# Microcontroller_IO.net
KiCad netlist of a schematic drawn in Altium Designer
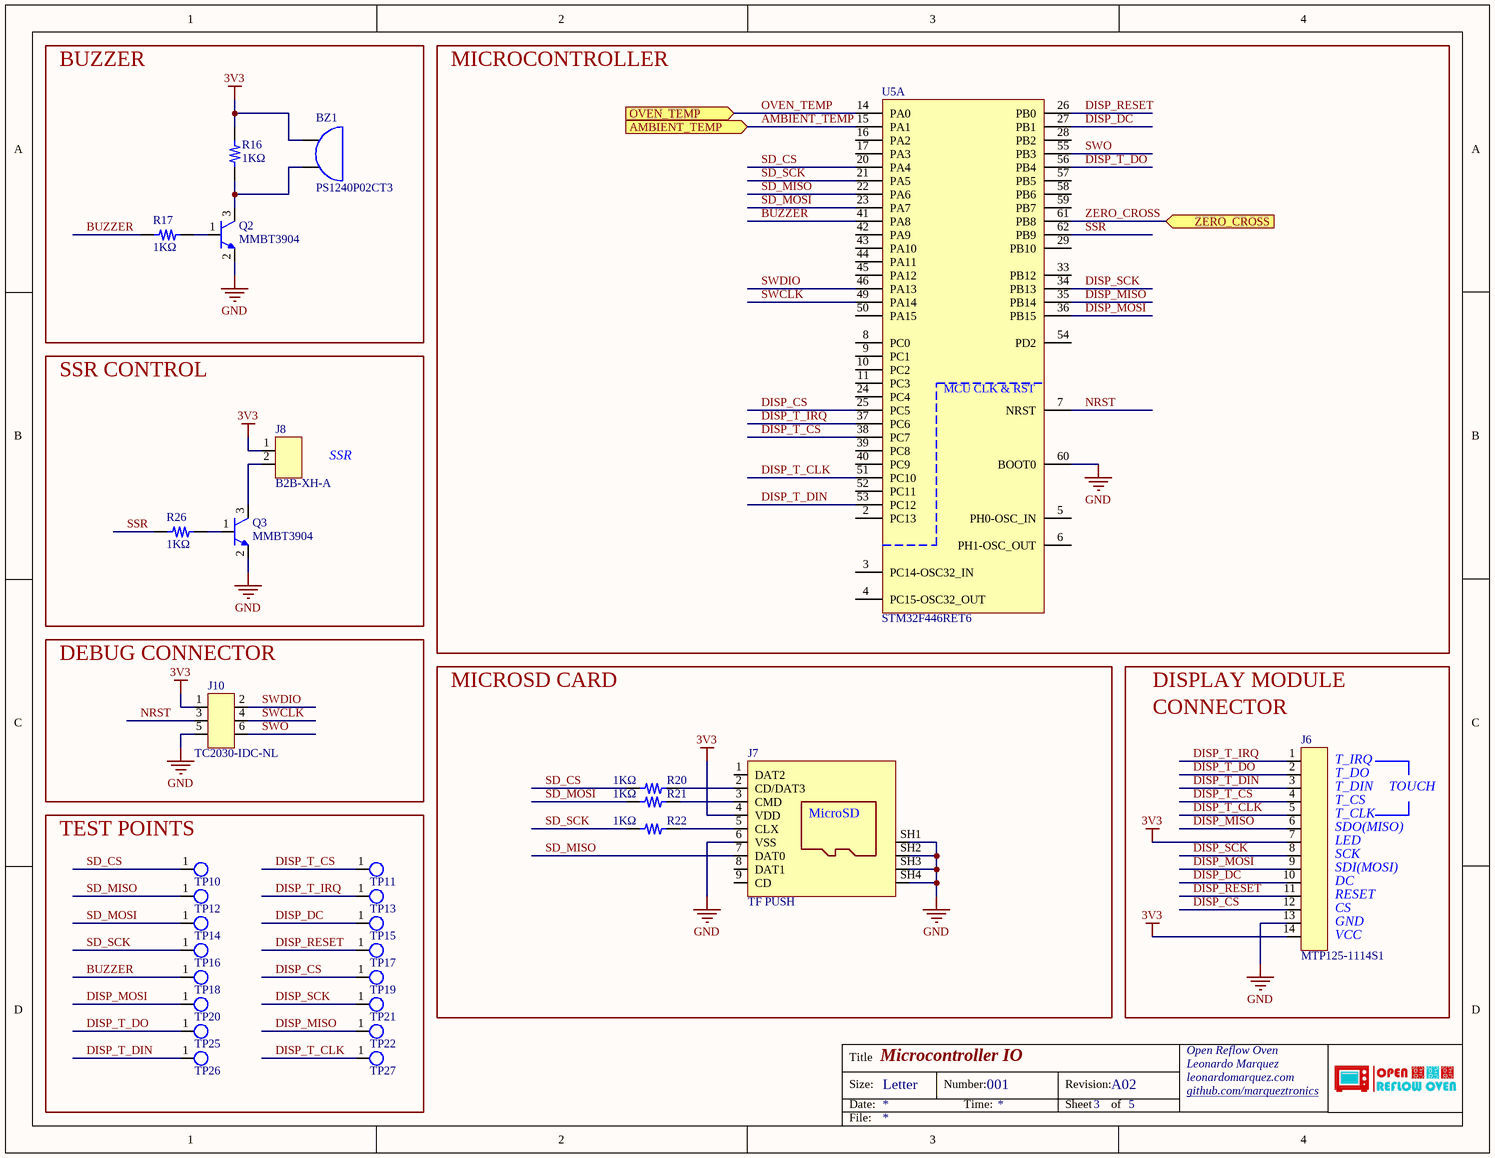
[diagram p0: Microcontroller IO.SchDoc]

(export (version "E")
  (design (tool "Eeschema 10.0.6"))
  (components
    (comp (ref "BZ1")
      (value "PS1240P02CT3")
      (footprint "PS1240P02CT3")
      (description "60dB Externally Driven Externally Driven 4kHz Plugin,D=12.2mm Buzzers ROHS")
      (fields (field (name "MANUFACTURER") "TDK"))
      (libsource (lib "REFLOW_CONTROLLER") (part "BZ-4KHZ-30V-PS1240P02CT3"))
    )
    (comp (ref "J6")
      (value "MTP125-1114S1")
      (footprint "MTP125-1114S1")
      (description "14P 2.54mm Single Row 1x14P Plugin,P=2.54mm Pin Headers ROHS")
      (fields (field (name "MANUFACTURER") "MINTRON"))
      (libsource (lib "REFLOW_CONTROLLER") (part "J-14P-HDR-MALE-2.54MM-MTP125-1114S1"))
    )
    (comp (ref "J7")
      (value "TF PUSH")
      (footprint "TF_PUSH")
      (fields (field (name "MANUFACTURER") "SHOU HAN"))
      (libsource (lib "REFLOW_CONTROLLER") (part "J-MICROSD-TF_PUSH"))
    )
    (comp (ref "J8")
      (value "B2B-XH-A")
      (footprint "B2B-XH-A")
      (description "1x2P 2P XH 1 2.5mm 2 Brass Plugin,P=2.5mm Wire To Board Connector ROHS")
      (fields
        (field (name "MANUFACTURER") "JST")
        (field (name "MANUFACTURER PART NUMBER") "B2B-XH-A(LF)(SN)")
      )
      (libsource (lib "REFLOW_CONTROLLER") (part "J-2P-2.5MM-B2B-XH-A"))
    )
    (comp (ref "J10")
      (value "TC2030-IDC-NL")
      (footprint "TC2030-IDC-NL-FP")
      (description "“No Legs” 6-pin Plug-of-Nails™ Cable fitted with a 6-pin 0.1″ pitch ribbon connector")
      (fields (field (name "MANUFACTURER") "Tag-Connect"))
      (libsource (lib "REFLOW_CONTROLLER") (part "J-6P-TAG-CONNECT-TC2030-IDC-NL-FP"))
    )
    (comp (ref "Q2")
      (value "MMBT3904")
      (footprint "SOT-23")
      (description "40V 250mW 200mA NPN SOT-23 Bipolar Transistors - BJT ROHS")
      (fields (field (name "MANUFACTURER") "Nexperia"))
      (libsource (lib "REFLOW_CONTROLLER") (part "Q-NPN-40V-0.2A-SOT-23"))
    )
    (comp (ref "Q3")
      (value "MMBT3904")
      (footprint "SOT-23")
      (description "40V 250mW 200mA NPN SOT-23 Bipolar Transistors - BJT ROHS")
      (fields (field (name "MANUFACTURER") "Nexperia"))
      (libsource (lib "REFLOW_CONTROLLER") (part "Q-NPN-40V-0.2A-SOT-23"))
    )
    (comp (ref "R16")
      (value "1KΩ")
      (footprint "R0603")
      (description "100mW Thick Film Resistors 75V ±100ppm/℃ ±1% 1kΩ 0603 Chip Resistor - Surface Mount ROHS")
      (fields
        (field (name "MANUFACTURER") "Yageo")
        (field (name "MANUFACTURER PART NUMBER") "RC0603FR-071KL")
      )
      (libsource (lib "REFLOW_CONTROLLER") (part "R-1K-1/10W-R0603"))
    )
    (comp (ref "R17")
      (value "1KΩ")
      (footprint "R0603")
      (description "100mW Thick Film Resistors 75V ±100ppm/℃ ±1% 1kΩ 0603 Chip Resistor - Surface Mount ROHS")
      (fields
        (field (name "MANUFACTURER") "Yageo")
        (field (name "MANUFACTURER PART NUMBER") "RC0603FR-071KL")
      )
      (libsource (lib "REFLOW_CONTROLLER") (part "R-1K-1/10W-R0603"))
    )
    (comp (ref "R20")
      (value "1KΩ")
      (footprint "R0603")
      (description "100mW Thick Film Resistors 75V ±100ppm/℃ ±1% 1kΩ 0603 Chip Resistor - Surface Mount ROHS")
      (fields
        (field (name "MANUFACTURER") "Yageo")
        (field (name "MANUFACTURER PART NUMBER") "RC0603FR-071KL")
      )
      (libsource (lib "REFLOW_CONTROLLER") (part "R-1K-1/10W-R0603"))
    )
    (comp (ref "R21")
      (value "1KΩ")
      (footprint "R0603")
      (description "100mW Thick Film Resistors 75V ±100ppm/℃ ±1% 1kΩ 0603 Chip Resistor - Surface Mount ROHS")
      (fields
        (field (name "MANUFACTURER") "Yageo")
        (field (name "MANUFACTURER PART NUMBER") "RC0603FR-071KL")
      )
      (libsource (lib "REFLOW_CONTROLLER") (part "R-1K-1/10W-R0603"))
    )
    (comp (ref "R22")
      (value "1KΩ")
      (footprint "R0603")
      (description "100mW Thick Film Resistors 75V ±100ppm/℃ ±1% 1kΩ 0603 Chip Resistor - Surface Mount ROHS")
      (fields
        (field (name "MANUFACTURER") "Yageo")
        (field (name "MANUFACTURER PART NUMBER") "RC0603FR-071KL")
      )
      (libsource (lib "REFLOW_CONTROLLER") (part "R-1K-1/10W-R0603"))
    )
    (comp (ref "R26")
      (value "1KΩ")
      (footprint "R0603")
      (description "100mW Thick Film Resistors 75V ±100ppm/℃ ±1% 1kΩ 0603 Chip Resistor - Surface Mount ROHS")
      (fields
        (field (name "MANUFACTURER") "Yageo")
        (field (name "MANUFACTURER PART NUMBER") "RC0603FR-071KL")
      )
      (libsource (lib "REFLOW_CONTROLLER") (part "R-1K-1/10W-R0603"))
    )
    (comp (ref "TP10")
      (value "TP-1MM-ROUND")
      (footprint "TP-1MM-ROUND")
      (description "Round Test Point 1mm Dia")
      (libsource (lib "REFLOW_CONTROLLER") (part "TP-1MM-ROUND"))
    )
    (comp (ref "TP11")
      (value "TP-1MM-ROUND")
      (footprint "TP-1MM-ROUND")
      (description "Round Test Point 1mm Dia")
      (libsource (lib "REFLOW_CONTROLLER") (part "TP-1MM-ROUND"))
    )
    (comp (ref "TP12")
      (value "TP-1MM-ROUND")
      (footprint "TP-1MM-ROUND")
      (description "Round Test Point 1mm Dia")
      (libsource (lib "REFLOW_CONTROLLER") (part "TP-1MM-ROUND"))
    )
    (comp (ref "TP13")
      (value "TP-1MM-ROUND")
      (footprint "TP-1MM-ROUND")
      (description "Round Test Point 1mm Dia")
      (libsource (lib "REFLOW_CONTROLLER") (part "TP-1MM-ROUND"))
    )
    (comp (ref "TP14")
      (value "TP-1MM-ROUND")
      (footprint "TP-1MM-ROUND")
      (description "Round Test Point 1mm Dia")
      (libsource (lib "REFLOW_CONTROLLER") (part "TP-1MM-ROUND"))
    )
    (comp (ref "TP15")
      (value "TP-1MM-ROUND")
      (footprint "TP-1MM-ROUND")
      (description "Round Test Point 1mm Dia")
      (libsource (lib "REFLOW_CONTROLLER") (part "TP-1MM-ROUND"))
    )
    (comp (ref "TP16")
      (value "TP-1MM-ROUND")
      (footprint "TP-1MM-ROUND")
      (description "Round Test Point 1mm Dia")
      (libsource (lib "REFLOW_CONTROLLER") (part "TP-1MM-ROUND"))
    )
    (comp (ref "TP17")
      (value "TP-1MM-ROUND")
      (footprint "TP-1MM-ROUND")
      (description "Round Test Point 1mm Dia")
      (libsource (lib "REFLOW_CONTROLLER") (part "TP-1MM-ROUND"))
    )
    (comp (ref "TP18")
      (value "TP-1MM-ROUND")
      (footprint "TP-1MM-ROUND")
      (description "Round Test Point 1mm Dia")
      (libsource (lib "REFLOW_CONTROLLER") (part "TP-1MM-ROUND"))
    )
    (comp (ref "TP19")
      (value "TP-1MM-ROUND")
      (footprint "TP-1MM-ROUND")
      (description "Round Test Point 1mm Dia")
      (libsource (lib "REFLOW_CONTROLLER") (part "TP-1MM-ROUND"))
    )
    (comp (ref "TP20")
      (value "TP-1MM-ROUND")
      (footprint "TP-1MM-ROUND")
      (description "Round Test Point 1mm Dia")
      (libsource (lib "REFLOW_CONTROLLER") (part "TP-1MM-ROUND"))
    )
    (comp (ref "TP21")
      (value "TP-1MM-ROUND")
      (footprint "TP-1MM-ROUND")
      (description "Round Test Point 1mm Dia")
      (libsource (lib "REFLOW_CONTROLLER") (part "TP-1MM-ROUND"))
    )
    (comp (ref "TP22")
      (value "TP-1MM-ROUND")
      (footprint "TP-1MM-ROUND")
      (description "Round Test Point 1mm Dia")
      (libsource (lib "REFLOW_CONTROLLER") (part "TP-1MM-ROUND"))
    )
    (comp (ref "TP25")
      (value "TP-1MM-ROUND")
      (footprint "TP-1MM-ROUND")
      (description "Round Test Point 1mm Dia")
      (libsource (lib "REFLOW_CONTROLLER") (part "TP-1MM-ROUND"))
    )
    (comp (ref "TP26")
      (value "TP-1MM-ROUND")
      (footprint "TP-1MM-ROUND")
      (description "Round Test Point 1mm Dia")
      (libsource (lib "REFLOW_CONTROLLER") (part "TP-1MM-ROUND"))
    )
    (comp (ref "TP27")
      (value "TP-1MM-ROUND")
      (footprint "TP-1MM-ROUND")
      (description "Round Test Point 1mm Dia")
      (libsource (lib "REFLOW_CONTROLLER") (part "TP-1MM-ROUND"))
    )
    (comp (ref "U5")
      (value "STM32F446RET6")
      (footprint "LQFP-64_10X10")
      (description "512KB 1.7V~3.6V ARM-M4 128KB 180MHz FLASH 50 LQFP-64(10x10) Microcontrollers (MCU/MPU/SOC) ROHS")
      (fields (field (name "MANUFACTURER") "STMicroelectronics"))
      (libsource (lib "REFLOW_CONTROLLER") (part "U-STM32F446RET6-LQFP-64_10X10"))
    )
  )
  (nets
    (net (code "1") (name "/AMBIENT_TEMP") (class "Default")
      (node (ref "U5") (pin "15") (pinfunction "PA1_15") (pintype "passive"))
    )
    (net (code "2") (name "/BUZZER") (class "Default")
      (node (ref "R17") (pin "2") (pinfunction "2_2") (pintype "passive"))
      (node (ref "TP18") (pin "1") (pinfunction "1_1") (pintype "passive"))
      (node (ref "U5") (pin "41") (pinfunction "PA8_41") (pintype "passive"))
    )
    (net (code "3") (name "/DISP_CS") (class "Default")
      (node (ref "J6") (pin "12") (pinfunction "12_12") (pintype "passive"))
      (node (ref "TP19") (pin "1") (pinfunction "1_1") (pintype "passive"))
      (node (ref "U5") (pin "25") (pinfunction "PC5_25") (pintype "passive"))
    )
    (net (code "4") (name "/DISP_DC") (class "Default")
      (node (ref "J6") (pin "10") (pinfunction "10_10") (pintype "passive"))
      (node (ref "TP15") (pin "1") (pinfunction "1_1") (pintype "passive"))
      (node (ref "U5") (pin "27") (pinfunction "PB1_27") (pintype "passive"))
    )
    (net (code "5") (name "/DISP_MISO") (class "Default")
      (node (ref "J6") (pin "6") (pinfunction "6_6") (pintype "passive"))
      (node (ref "TP22") (pin "1") (pinfunction "1_1") (pintype "passive"))
      (node (ref "U5") (pin "35") (pinfunction "PB14_35") (pintype "passive"))
    )
    (net (code "6") (name "/DISP_MOSI") (class "Default")
      (node (ref "J6") (pin "9") (pinfunction "9_9") (pintype "passive"))
      (node (ref "TP20") (pin "1") (pinfunction "1_1") (pintype "passive"))
      (node (ref "U5") (pin "36") (pinfunction "PB15_36") (pintype "passive"))
    )
    (net (code "7") (name "/DISP_RESET") (class "Default")
      (node (ref "J6") (pin "11") (pinfunction "11_11") (pintype "passive"))
      (node (ref "TP17") (pin "1") (pinfunction "1_1") (pintype "passive"))
      (node (ref "U5") (pin "26") (pinfunction "PB0_26") (pintype "passive"))
    )
    (net (code "8") (name "/DISP_SCK") (class "Default")
      (node (ref "J6") (pin "8") (pinfunction "8_8") (pintype "passive"))
      (node (ref "TP21") (pin "1") (pinfunction "1_1") (pintype "passive"))
      (node (ref "U5") (pin "34") (pinfunction "PB13_34") (pintype "passive"))
    )
    (net (code "9") (name "/DISP_T_CLK") (class "Default")
      (node (ref "J6") (pin "5") (pinfunction "5_5") (pintype "passive"))
      (node (ref "TP27") (pin "1") (pinfunction "1_1") (pintype "passive"))
      (node (ref "U5") (pin "51") (pinfunction "PC10_51") (pintype "passive"))
    )
    (net (code "10") (name "/DISP_T_CS") (class "Default")
      (node (ref "J6") (pin "4") (pinfunction "4_4") (pintype "passive"))
      (node (ref "TP11") (pin "1") (pinfunction "1_1") (pintype "passive"))
      (node (ref "U5") (pin "38") (pinfunction "PC7_38") (pintype "passive"))
    )
    (net (code "11") (name "/DISP_T_DIN") (class "Default")
      (node (ref "J6") (pin "3") (pinfunction "3_3") (pintype "passive"))
      (node (ref "TP26") (pin "1") (pinfunction "1_1") (pintype "passive"))
      (node (ref "U5") (pin "53") (pinfunction "PC12_53") (pintype "passive"))
    )
    (net (code "12") (name "/DISP_T_DO") (class "Default")
      (node (ref "J6") (pin "2") (pinfunction "2_2") (pintype "passive"))
      (node (ref "TP25") (pin "1") (pinfunction "1_1") (pintype "passive"))
      (node (ref "U5") (pin "56") (pinfunction "PB4_56") (pintype "passive"))
    )
    (net (code "13") (name "/DISP_T_IRQ") (class "Default")
      (node (ref "J6") (pin "1") (pinfunction "1_1") (pintype "passive"))
      (node (ref "TP13") (pin "1") (pinfunction "1_1") (pintype "passive"))
      (node (ref "U5") (pin "37") (pinfunction "PC6_37") (pintype "passive"))
    )
    (net (code "14") (name "/NRST") (class "Default")
      (node (ref "J10") (pin "3") (pinfunction "3_3") (pintype "passive"))
      (node (ref "U5") (pin "7") (pinfunction "NRST_7") (pintype "passive"))
    )
    (net (code "15") (name "/OVEN_TEMP") (class "Default")
      (node (ref "U5") (pin "14") (pinfunction "PA0_14") (pintype "passive"))
    )
    (net (code "16") (name "/SD_CS") (class "Default")
      (node (ref "R20") (pin "2") (pinfunction "2_2") (pintype "passive"))
      (node (ref "TP10") (pin "1") (pinfunction "1_1") (pintype "passive"))
      (node (ref "U5") (pin "20") (pinfunction "PA4_20") (pintype "passive"))
    )
    (net (code "17") (name "/SD_MISO") (class "Default")
      (node (ref "J7") (pin "7") (pinfunction "DAT0_7") (pintype "passive"))
      (node (ref "TP12") (pin "1") (pinfunction "1_1") (pintype "passive"))
      (node (ref "U5") (pin "22") (pinfunction "PA6_22") (pintype "passive"))
    )
    (net (code "18") (name "/SD_MOSI") (class "Default")
      (node (ref "R21") (pin "2") (pinfunction "2_2") (pintype "passive"))
      (node (ref "TP14") (pin "1") (pinfunction "1_1") (pintype "passive"))
      (node (ref "U5") (pin "23") (pinfunction "PA7_23") (pintype "passive"))
    )
    (net (code "19") (name "/SD_SCK") (class "Default")
      (node (ref "R22") (pin "2") (pinfunction "2_2") (pintype "passive"))
      (node (ref "TP16") (pin "1") (pinfunction "1_1") (pintype "passive"))
      (node (ref "U5") (pin "21") (pinfunction "PA5_21") (pintype "passive"))
    )
    (net (code "20") (name "/SSR") (class "Default")
      (node (ref "R26") (pin "2") (pinfunction "2_2") (pintype "passive"))
      (node (ref "U5") (pin "62") (pinfunction "PB9_62") (pintype "passive"))
    )
    (net (code "21") (name "/SWCLK") (class "Default")
      (node (ref "J10") (pin "4") (pinfunction "4_4") (pintype "passive"))
      (node (ref "U5") (pin "49") (pinfunction "PA14_49") (pintype "passive"))
    )
    (net (code "22") (name "/SWDIO") (class "Default")
      (node (ref "J10") (pin "2") (pinfunction "2_2") (pintype "passive"))
      (node (ref "U5") (pin "46") (pinfunction "PA13_46") (pintype "passive"))
    )
    (net (code "23") (name "/SWO") (class "Default")
      (node (ref "J10") (pin "6") (pinfunction "6_6") (pintype "passive"))
      (node (ref "U5") (pin "55") (pinfunction "PB3_55") (pintype "passive"))
    )
    (net (code "24") (name "/ZERO_CROSS") (class "Default")
      (node (ref "U5") (pin "61") (pinfunction "PB8_61") (pintype "passive"))
    )
    (net (code "25") (name "3V3") (class "Default")
      (node (ref "BZ1") (pin "1") (pinfunction "1_1") (pintype "passive"))
      (node (ref "J10") (pin "1") (pinfunction "1_1") (pintype "passive"))
      (node (ref "J6") (pin "14") (pinfunction "14_14") (pintype "passive"))
      (node (ref "J6") (pin "7") (pinfunction "7_7") (pintype "passive"))
      (node (ref "J7") (pin "4") (pinfunction "VDD_4") (pintype "passive"))
      (node (ref "J8") (pin "1") (pinfunction "1_1") (pintype "passive"))
      (node (ref "R16") (pin "2") (pinfunction "2_2") (pintype "passive"))
    )
    (net (code "26") (name "GND") (class "Default")
      (node (ref "J10") (pin "5") (pinfunction "5_5") (pintype "passive"))
      (node (ref "J6") (pin "13") (pinfunction "13_13") (pintype "passive"))
      (node (ref "J7") (pin "6") (pinfunction "VSS_6") (pintype "passive"))
      (node (ref "J7") (pin "SH1") (pinfunction "SHIELD_SH1") (pintype "passive"))
      (node (ref "J7") (pin "SH2") (pinfunction "SHIELD_SH2") (pintype "passive"))
      (node (ref "J7") (pin "SH3") (pinfunction "SHIELD_SH3") (pintype "passive"))
      (node (ref "J7") (pin "SH4") (pinfunction "SHIELD_SH4") (pintype "passive"))
      (node (ref "Q2") (pin "2") (pinfunction "E_2") (pintype "passive"))
      (node (ref "Q3") (pin "2") (pinfunction "E_2") (pintype "passive"))
      (node (ref "U5") (pin "60") (pinfunction "BOOT0_60") (pintype "passive"))
    )
    (net (code "27") (name "Net-(J7-CD{slash}DAT3)") (class "Default")
      (node (ref "J7") (pin "2") (pinfunction "CD/DAT3_2") (pintype "passive"))
      (node (ref "R20") (pin "1") (pinfunction "1_1") (pintype "passive"))
    )
    (net (code "28") (name "Net-(J7-CLX)") (class "Default")
      (node (ref "J7") (pin "5") (pinfunction "CLX_5") (pintype "passive"))
      (node (ref "R22") (pin "1") (pinfunction "1_1") (pintype "passive"))
    )
    (net (code "29") (name "Net-(J7-CMD)") (class "Default")
      (node (ref "J7") (pin "3") (pinfunction "CMD_3") (pintype "passive"))
      (node (ref "R21") (pin "1") (pinfunction "1_1") (pintype "passive"))
    )
    (net (code "30") (name "Net-(Q2-B)") (class "Default")
      (node (ref "Q2") (pin "1") (pinfunction "B_1") (pintype "passive"))
      (node (ref "R17") (pin "1") (pinfunction "1_1") (pintype "passive"))
    )
    (net (code "31") (name "Net-(Q2-C)") (class "Default")
      (node (ref "BZ1") (pin "2") (pinfunction "2_2") (pintype "passive"))
      (node (ref "Q2") (pin "3") (pinfunction "C_3") (pintype "passive"))
      (node (ref "R16") (pin "1") (pinfunction "1_1") (pintype "passive"))
    )
    (net (code "32") (name "Net-(Q3-B)") (class "Default")
      (node (ref "Q3") (pin "1") (pinfunction "B_1") (pintype "passive"))
      (node (ref "R26") (pin "1") (pinfunction "1_1") (pintype "passive"))
    )
    (net (code "33") (name "Net-(Q3-C)") (class "Default")
      (node (ref "J8") (pin "2") (pinfunction "2_2") (pintype "passive"))
      (node (ref "Q3") (pin "3") (pinfunction "C_3") (pintype "passive"))
    )
    (net (code "34") (name "unconnected-(J7-CD-Pad9)") (class "Default")
      (node (ref "J7") (pin "9") (pinfunction "CD_9") (pintype "passive"))
    )
    (net (code "35") (name "unconnected-(J7-DAT1-Pad8)") (class "Default")
      (node (ref "J7") (pin "8") (pinfunction "DAT1_8") (pintype "passive"))
    )
    (net (code "36") (name "unconnected-(J7-DAT2-Pad1)") (class "Default")
      (node (ref "J7") (pin "1") (pinfunction "DAT2_1") (pintype "passive"))
    )
    (net (code "37") (name "unconnected-(U5A-PA2-Pad16)") (class "Default")
      (node (ref "U5") (pin "16") (pinfunction "PA2_16") (pintype "passive"))
    )
    (net (code "38") (name "unconnected-(U5A-PA3-Pad17)") (class "Default")
      (node (ref "U5") (pin "17") (pinfunction "PA3_17") (pintype "passive"))
    )
    (net (code "39") (name "unconnected-(U5A-PA9-Pad42)") (class "Default")
      (node (ref "U5") (pin "42") (pinfunction "PA9_42") (pintype "passive"))
    )
    (net (code "40") (name "unconnected-(U5A-PA10-Pad43)") (class "Default")
      (node (ref "U5") (pin "43") (pinfunction "PA10_43") (pintype "passive"))
    )
    (net (code "41") (name "unconnected-(U5A-PA11-Pad44)") (class "Default")
      (node (ref "U5") (pin "44") (pinfunction "PA11_44") (pintype "passive"))
    )
    (net (code "42") (name "unconnected-(U5A-PA12-Pad45)") (class "Default")
      (node (ref "U5") (pin "45") (pinfunction "PA12_45") (pintype "passive"))
    )
    (net (code "43") (name "unconnected-(U5A-PA15-Pad50)") (class "Default")
      (node (ref "U5") (pin "50") (pinfunction "PA15_50") (pintype "passive"))
    )
    (net (code "44") (name "unconnected-(U5A-PB2-Pad28)") (class "Default")
      (node (ref "U5") (pin "28") (pinfunction "PB2_28") (pintype "passive"))
    )
    (net (code "45") (name "unconnected-(U5A-PB5-Pad57)") (class "Default")
      (node (ref "U5") (pin "57") (pinfunction "PB5_57") (pintype "passive"))
    )
    (net (code "46") (name "unconnected-(U5A-PB6-Pad58)") (class "Default")
      (node (ref "U5") (pin "58") (pinfunction "PB6_58") (pintype "passive"))
    )
    (net (code "47") (name "unconnected-(U5A-PB7-Pad59)") (class "Default")
      (node (ref "U5") (pin "59") (pinfunction "PB7_59") (pintype "passive"))
    )
    (net (code "48") (name "unconnected-(U5A-PB10-Pad29)") (class "Default")
      (node (ref "U5") (pin "29") (pinfunction "PB10_29") (pintype "passive"))
    )
    (net (code "49") (name "unconnected-(U5A-PB12-Pad33)") (class "Default")
      (node (ref "U5") (pin "33") (pinfunction "PB12_33") (pintype "passive"))
    )
    (net (code "50") (name "unconnected-(U5A-PC0-Pad8)") (class "Default")
      (node (ref "U5") (pin "8") (pinfunction "PC0_8") (pintype "passive"))
    )
    (net (code "51") (name "unconnected-(U5A-PC1-Pad9)") (class "Default")
      (node (ref "U5") (pin "9") (pinfunction "PC1_9") (pintype "passive"))
    )
    (net (code "52") (name "unconnected-(U5A-PC2-Pad10)") (class "Default")
      (node (ref "U5") (pin "10") (pinfunction "PC2_10") (pintype "passive"))
    )
    (net (code "53") (name "unconnected-(U5A-PC3-Pad11)") (class "Default")
      (node (ref "U5") (pin "11") (pinfunction "PC3_11") (pintype "passive"))
    )
    (net (code "54") (name "unconnected-(U5A-PC4-Pad24)") (class "Default")
      (node (ref "U5") (pin "24") (pinfunction "PC4_24") (pintype "passive"))
    )
    (net (code "55") (name "unconnected-(U5A-PC8-Pad39)") (class "Default")
      (node (ref "U5") (pin "39") (pinfunction "PC8_39") (pintype "passive"))
    )
    (net (code "56") (name "unconnected-(U5A-PC9-Pad40)") (class "Default")
      (node (ref "U5") (pin "40") (pinfunction "PC9_40") (pintype "passive"))
    )
    (net (code "57") (name "unconnected-(U5A-PC11-Pad52)") (class "Default")
      (node (ref "U5") (pin "52") (pinfunction "PC11_52") (pintype "passive"))
    )
    (net (code "58") (name "unconnected-(U5A-PC13-Pad2)") (class "Default")
      (node (ref "U5") (pin "2") (pinfunction "PC13_2") (pintype "passive"))
    )
    (net (code "59") (name "unconnected-(U5A-PC14-OSC32_IN-Pad3)") (class "Default")
      (node (ref "U5") (pin "3") (pinfunction "PC14-OSC32_IN_3") (pintype "passive"))
    )
    (net (code "60") (name "unconnected-(U5A-PC15-OSC32_OUT-Pad4)") (class "Default")
      (node (ref "U5") (pin "4") (pinfunction "PC15-OSC32_OUT_4") (pintype "passive"))
    )
    (net (code "61") (name "unconnected-(U5A-PD2-Pad54)") (class "Default")
      (node (ref "U5") (pin "54") (pinfunction "PD2_54") (pintype "passive"))
    )
    (net (code "62") (name "unconnected-(U5A-PH0-OSC_IN-Pad5)") (class "Default")
      (node (ref "U5") (pin "5") (pinfunction "PH0-OSC_IN_5") (pintype "passive"))
    )
    (net (code "63") (name "unconnected-(U5A-PH1-OSC_OUT-Pad6)") (class "Default")
      (node (ref "U5") (pin "6") (pinfunction "PH1-OSC_OUT_6") (pintype "passive"))
    )
  )
)
